# SCH_Gateway.net
KiCad netlist of a schematic drawn in EasyEDA
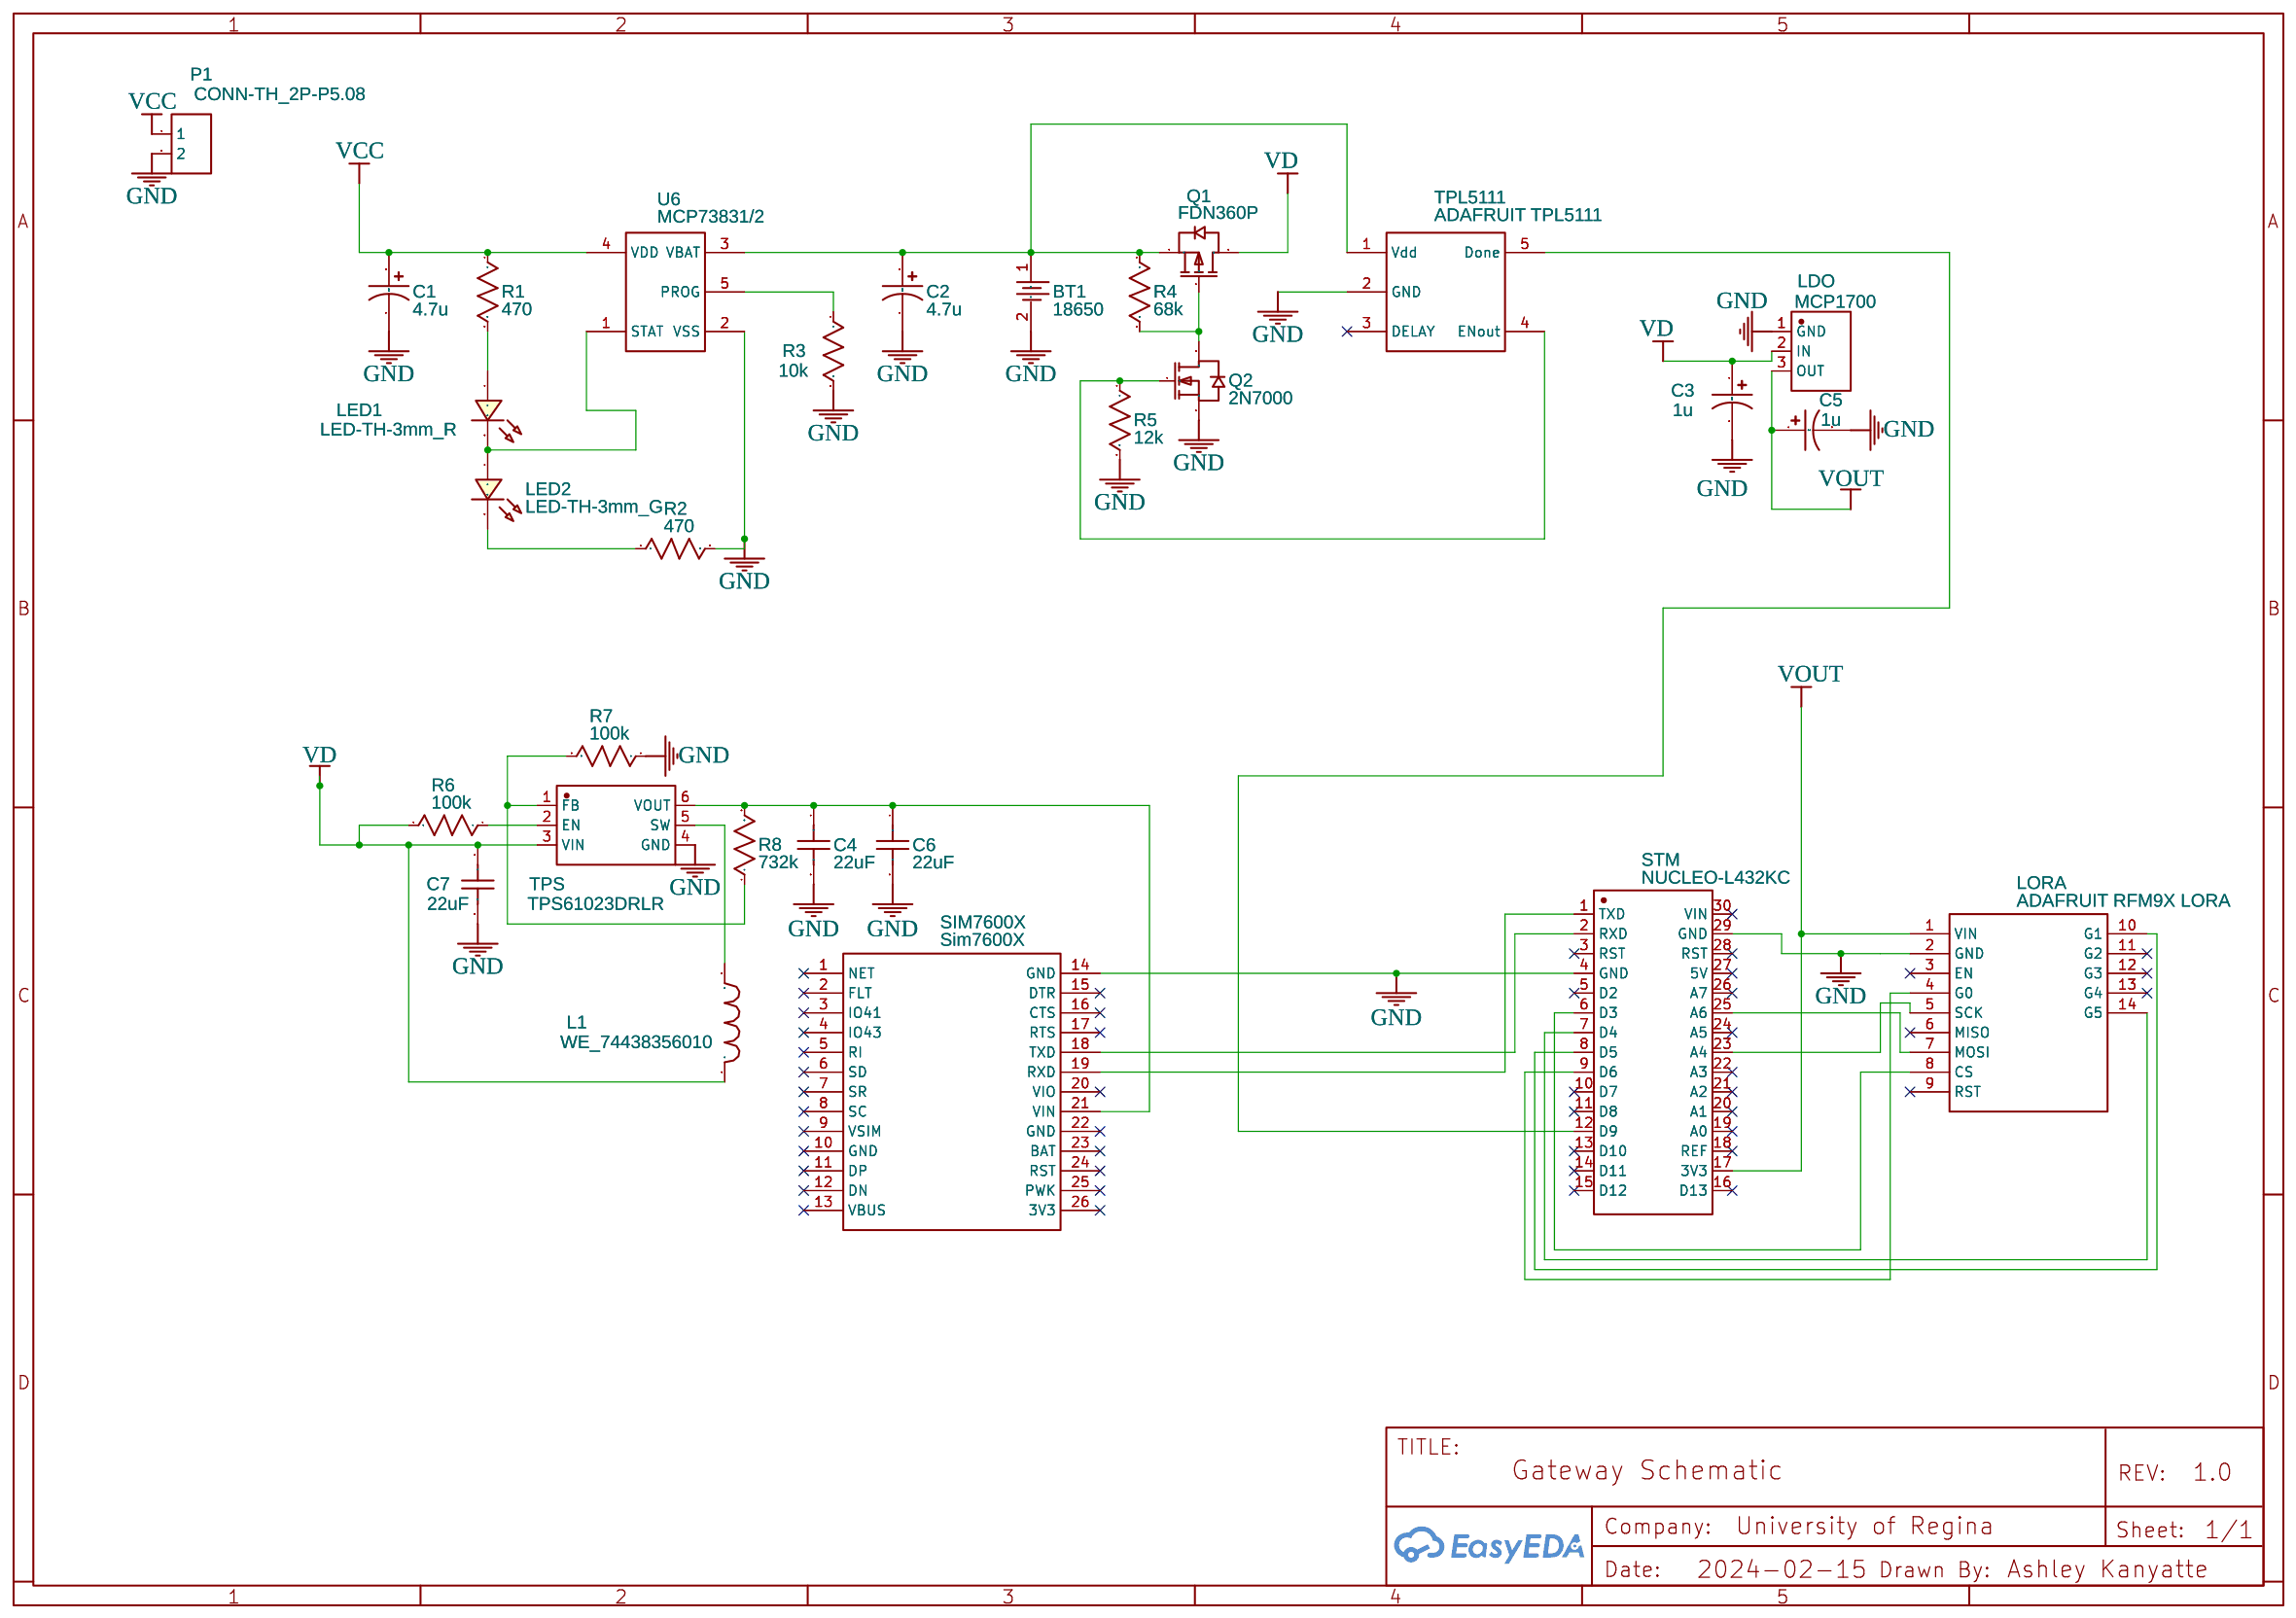
[diagram p0: schematic sheet]

(export (version "E")
  (design (tool "Eeschema 10.0.6"))
  (components
    (comp (ref "BT1")
      (value "18650")
      (fields
        (field (name "Manufacturer Part") "BH-18650-A5BJ001")
        (field (name "Manufacturer") "MYOUNG(美阳)")
      )
      (libsource (lib "") (part "BH-18650-A5BJ001"))
    )
    (comp (ref "C1") (value "4.7u") (libsource (lib "") (part "CE_TH_D5.0×F2.0_US_1")))
    (comp (ref "C2") (value "4.7u") (libsource (lib "") (part "CE_TH_D5.0×F2.0_US")))
    (comp (ref "C3") (value "1u") (libsource (lib "") (part "CE_TH_D5.0×F2.0_US")))
    (comp (ref "C4")
      (value "22uF")
      (fields
        (field (name "Manufacturer Part") "RDEC71E226K3K1H03B")
        (field (name "Manufacturer") "muRata(村田)")
      )
      (libsource (lib "") (part "RDEC71E226K3K1H03B"))
    )
    (comp (ref "C5") (value "1u") (libsource (lib "") (part "CE_TH_D5.0×F2.0_US_2")))
    (comp (ref "C6")
      (value "22uF")
      (fields
        (field (name "Manufacturer Part") "RDEC71E226K3K1H03B")
        (field (name "Manufacturer") "muRata(村田)")
      )
      (libsource (lib "") (part "RDEC71E226K3K1H03B"))
    )
    (comp (ref "C7")
      (value "22uF")
      (fields
        (field (name "Manufacturer Part") "RDEC71E226K3K1H03B")
        (field (name "Manufacturer") "muRata(村田)")
      )
      (libsource (lib "") (part "RDEC71E226K3K1H03B"))
    )
    (comp (ref "L1")
      (value "WE_74438356010")
      (fields
        (field (name "Manufacturer Part") "74438356010")
        (field (name "Manufacturer") "Wurth Elektronik")
      )
      (libsource (lib "") (part "WE_74438356010"))
    )
    (comp (ref "LDO")
      (value "MCP1700")
      (fields
        (field (name "Manufacturer Part") "MCP1700-3302E/TO")
        (field (name "Manufacturer") "MICROCHIP(美国微芯)")
      )
      (libsource (lib "") (part "MCP1700-3302E/TO"))
    )
    (comp (ref "LED1")
      (value "LED-TH-3mm_R")
      (fields
        (field (name "Manufacturer Part") "204-10SDRD/S530-A3-L")
        (field (name "Manufacturer") "EVERLIGHT(台湾亿光)")
      )
      (libsource (lib "") (part "LED-TH-3mm_R"))
    )
    (comp (ref "LED2")
      (value "LED-TH-3mm_G")
      (fields
        (field (name "Manufacturer Part") "204-10SYGD/S530-E3")
        (field (name "Manufacturer") "EVERLIGHT(台湾亿光)")
      )
      (libsource (lib "") (part "LED-TH-3mm_G"))
    )
    (comp (ref "LORA")
      (value "ADAFRUIT RFM9X LORA")
      (fields (field (name "Manufacturer Part") "3072") (field (name "Manufacturer") "Adafruit"))
      (libsource (lib "") (part "ADAFRUIT RFM9X LORA"))
    )
    (comp (ref "P1") (value "CONN-TH_2P-P5.08") (libsource (lib "") (part "CONN-TH_2P-P5.08")))
    (comp (ref "Q1")
      (value "FDN360P")
      (fields (field (name "Manufacturer") "onsemi(安森美)"))
      (libsource (lib "") (part "FDN360P"))
    )
    (comp (ref "Q2")
      (value "2N7000")
      (fields (field (name "Manufacturer") "CJ(江苏长电/长晶)"))
      (libsource (lib "") (part "2N7000"))
    )
    (comp (ref "R1") (value "470") (libsource (lib "") (part "R_AXIAL-0.4_US")))
    (comp (ref "R2") (value "470") (libsource (lib "") (part "R_AXIAL-0.4_US_1")))
    (comp (ref "R3") (value "10k") (libsource (lib "") (part "R_AXIAL-0.4_US")))
    (comp (ref "R4") (value "68k") (libsource (lib "") (part "R_AXIAL-0.4_US")))
    (comp (ref "R5") (value "12k") (libsource (lib "") (part "R_AXIAL-0.4_US")))
    (comp (ref "R6") (value "100k") (libsource (lib "") (part "R_AXIAL-0.4_US_3")))
    (comp (ref "R7") (value "100k") (libsource (lib "") (part "R_AXIAL-0.4_US_3")))
    (comp (ref "R8") (value "732k") (libsource (lib "") (part "R_AXIAL-0.4_US_2")))
    (comp (ref "SIM7600X") (value "Sim7600X") (libsource (lib "") (part "Sim7600X")))
    (comp (ref "STM")
      (value "NUCLEO-L432KC")
      (fields (field (name "Manufacturer") "ST(意法半导体)"))
      (libsource (lib "") (part "NUCLEO-L432KC"))
    )
    (comp (ref "TPL5111")
      (value "ADAFRUIT TPL5111")
      (fields (field (name "Manufacturer Part") "3435"))
      (libsource (lib "") (part "ADAFRUIT TPL5111"))
    )
    (comp (ref "TPS")
      (value "TPS61023DRLR")
      (fields (field (name "Manufacturer") "TI(德州仪器)"))
      (libsource (lib "") (part "TPS61023DRLR"))
    )
    (comp (ref "U6")
      (value "MCP73831/2")
      (fields (field (name "Manufacturer") "Microchip"))
      (libsource (lib "") (part "MCP73831/2"))
    )
  )
  (nets
    (net (code "1") (name "GND") (class "Default")
      (node (ref "BT1") (pin "2") (pinfunction "2_2") (pintype "input"))
      (node (ref "C1") (pin "2") (pinfunction "2_2") (pintype "unspecified"))
      (node (ref "C2") (pin "2") (pinfunction "2_2") (pintype "unspecified"))
      (node (ref "C3") (pin "2") (pinfunction "2_2") (pintype "unspecified"))
      (node (ref "C4") (pin "2") (pinfunction "2_2") (pintype "unspecified"))
      (node (ref "C5") (pin "2") (pinfunction "2_2") (pintype "unspecified"))
      (node (ref "C6") (pin "2") (pinfunction "2_2") (pintype "unspecified"))
      (node (ref "C7") (pin "2") (pinfunction "2_2") (pintype "unspecified"))
      (node (ref "LDO") (pin "1") (pinfunction "GND_1") (pintype "unspecified"))
      (node (ref "LORA") (pin "2") (pinfunction "GND_2") (pintype "unspecified"))
      (node (ref "P1") (pin "2") (pinfunction "2_2") (pintype "unspecified"))
      (node (ref "Q2") (pin "1") (pinfunction "S_1") (pintype "unspecified"))
      (node (ref "R2") (pin "2") (pinfunction "2_2") (pintype "unspecified"))
      (node (ref "R3") (pin "2") (pinfunction "2_2") (pintype "unspecified"))
      (node (ref "R5") (pin "2") (pinfunction "2_2") (pintype "unspecified"))
      (node (ref "R7") (pin "1") (pinfunction "1_1") (pintype "unspecified"))
      (node (ref "SIM7600X") (pin "14") (pinfunction "GND_14") (pintype "unspecified"))
      (node (ref "STM") (pin "29") (pinfunction "GND_29") (pintype "unspecified"))
      (node (ref "STM") (pin "4") (pinfunction "GND_4") (pintype "unspecified"))
      (node (ref "TPL5111") (pin "2") (pinfunction "GND_2") (pintype "unspecified"))
      (node (ref "TPS") (pin "4") (pinfunction "GND_4") (pintype "unspecified"))
      (node (ref "U6") (pin "2") (pinfunction "VSS_2") (pintype "unspecified"))
    )
    (net (code "2") (name "Net-(LED1-Pad1)") (class "Default")
      (node (ref "LED1") (pin "1") (pinfunction "1_1") (pintype "unspecified"))
      (node (ref "R1") (pin "2") (pinfunction "2_2") (pintype "unspecified"))
    )
    (net (code "3") (name "Net-(LED2-Pad2)") (class "Default")
      (node (ref "LED2") (pin "2") (pinfunction "2_2") (pintype "unspecified"))
      (node (ref "R2") (pin "1") (pinfunction "1_1") (pintype "unspecified"))
    )
    (net (code "4") (name "Net-(LORA-CS)") (class "Default")
      (node (ref "LORA") (pin "8") (pinfunction "CS_8") (pintype "unspecified"))
      (node (ref "STM") (pin "6") (pinfunction "D3_6") (pintype "unspecified"))
    )
    (net (code "5") (name "Net-(LORA-G0)") (class "Default")
      (node (ref "LORA") (pin "4") (pinfunction "G0_4") (pintype "unspecified"))
      (node (ref "STM") (pin "9") (pinfunction "D6_9") (pintype "unspecified"))
    )
    (net (code "6") (name "Net-(LORA-G1)") (class "Default")
      (node (ref "LORA") (pin "10") (pinfunction "G1_10") (pintype "unspecified"))
      (node (ref "STM") (pin "8") (pinfunction "D5_8") (pintype "unspecified"))
    )
    (net (code "7") (name "Net-(LORA-G5)") (class "Default")
      (node (ref "LORA") (pin "14") (pinfunction "G5_14") (pintype "unspecified"))
      (node (ref "STM") (pin "7") (pinfunction "D4_7") (pintype "unspecified"))
    )
    (net (code "8") (name "Net-(LORA-MOSI)") (class "Default")
      (node (ref "LORA") (pin "7") (pinfunction "MOSI_7") (pintype "unspecified"))
      (node (ref "STM") (pin "25") (pinfunction "A6_25") (pintype "unspecified"))
    )
    (net (code "9") (name "Net-(LORA-SCK)") (class "Default")
      (node (ref "LORA") (pin "5") (pinfunction "SCK_5") (pintype "unspecified"))
      (node (ref "STM") (pin "23") (pinfunction "A4_23") (pintype "unspecified"))
    )
    (net (code "10") (name "Net-(Q1-G)") (class "Default")
      (node (ref "Q1") (pin "1") (pinfunction "G_1") (pintype "unspecified"))
      (node (ref "Q2") (pin "3") (pinfunction "D_3") (pintype "unspecified"))
      (node (ref "R4") (pin "2") (pinfunction "2_2") (pintype "unspecified"))
    )
    (net (code "11") (name "Net-(Q1-S)") (class "Default")
      (node (ref "BT1") (pin "1") (pinfunction "1_1") (pintype "input"))
      (node (ref "C2") (pin "1") (pinfunction "1_1") (pintype "unspecified"))
      (node (ref "Q1") (pin "2") (pinfunction "S_2") (pintype "unspecified"))
      (node (ref "R4") (pin "1") (pinfunction "1_1") (pintype "unspecified"))
      (node (ref "TPL5111") (pin "1") (pinfunction "Vdd_1") (pintype "unspecified"))
      (node (ref "U6") (pin "3") (pinfunction "VBAT_3") (pintype "unspecified"))
    )
    (net (code "12") (name "Net-(Q2-G)") (class "Default")
      (node (ref "Q2") (pin "2") (pinfunction "G_2") (pintype "unspecified"))
      (node (ref "R5") (pin "1") (pinfunction "1_1") (pintype "unspecified"))
      (node (ref "TPL5111") (pin "4") (pinfunction "ENout_4") (pintype "unspecified"))
    )
    (net (code "13") (name "Net-(SIM7600X-RXD)") (class "Default")
      (node (ref "SIM7600X") (pin "19") (pinfunction "RXD_19") (pintype "unspecified"))
      (node (ref "STM") (pin "1") (pinfunction "TXD_1") (pintype "unspecified"))
    )
    (net (code "14") (name "Net-(SIM7600X-TXD)") (class "Default")
      (node (ref "SIM7600X") (pin "18") (pinfunction "TXD_18") (pintype "unspecified"))
      (node (ref "STM") (pin "2") (pinfunction "RXD_2") (pintype "unspecified"))
    )
    (net (code "15") (name "Net-(SIM7600X-VIN)") (class "Default")
      (node (ref "C4") (pin "1") (pinfunction "1_1") (pintype "unspecified"))
      (node (ref "C6") (pin "1") (pinfunction "1_1") (pintype "unspecified"))
      (node (ref "R8") (pin "2") (pinfunction "2_2") (pintype "unspecified"))
      (node (ref "SIM7600X") (pin "21") (pinfunction "VIN_21") (pintype "unspecified"))
      (node (ref "TPS") (pin "6") (pinfunction "VOUT_6") (pintype "unspecified"))
    )
    (net (code "16") (name "Net-(STM-D9)") (class "Default")
      (node (ref "STM") (pin "12") (pinfunction "D9_12") (pintype "unspecified"))
      (node (ref "TPL5111") (pin "5") (pinfunction "Done_5") (pintype "unspecified"))
    )
    (net (code "17") (name "Net-(TPS-EN)") (class "Default")
      (node (ref "R6") (pin "1") (pinfunction "1_1") (pintype "unspecified"))
      (node (ref "TPS") (pin "2") (pinfunction "EN_2") (pintype "unspecified"))
    )
    (net (code "18") (name "Net-(TPS-FB)") (class "Default")
      (node (ref "R7") (pin "2") (pinfunction "2_2") (pintype "unspecified"))
      (node (ref "R8") (pin "1") (pinfunction "1_1") (pintype "unspecified"))
      (node (ref "TPS") (pin "1") (pinfunction "FB_1") (pintype "unspecified"))
    )
    (net (code "19") (name "Net-(TPS-SW)") (class "Default")
      (node (ref "L1") (pin "1") (pinfunction "1_1") (pintype "unspecified"))
      (node (ref "TPS") (pin "5") (pinfunction "SW_5") (pintype "unspecified"))
    )
    (net (code "20") (name "Net-(U6-PROG)") (class "Default")
      (node (ref "R3") (pin "1") (pinfunction "1_1") (pintype "unspecified"))
      (node (ref "U6") (pin "5") (pinfunction "PROG_5") (pintype "unspecified"))
    )
    (net (code "21") (name "Net-(U6-STAT)") (class "Default")
      (node (ref "LED1") (pin "2") (pinfunction "2_2") (pintype "unspecified"))
      (node (ref "LED2") (pin "1") (pinfunction "1_1") (pintype "unspecified"))
      (node (ref "U6") (pin "1") (pinfunction "STAT_1") (pintype "unspecified"))
    )
    (net (code "22") (name "VCC") (class "Default")
      (node (ref "C1") (pin "1") (pinfunction "1_1") (pintype "unspecified"))
      (node (ref "P1") (pin "1") (pinfunction "1_1") (pintype "unspecified"))
      (node (ref "R1") (pin "1") (pinfunction "1_1") (pintype "unspecified"))
      (node (ref "U6") (pin "4") (pinfunction "VDD_4") (pintype "unspecified"))
    )
    (net (code "23") (name "VD") (class "Default")
      (node (ref "C3") (pin "1") (pinfunction "1_1") (pintype "unspecified"))
      (node (ref "C7") (pin "1") (pinfunction "1_1") (pintype "unspecified"))
      (node (ref "L1") (pin "2") (pinfunction "2_2") (pintype "unspecified"))
      (node (ref "LDO") (pin "2") (pinfunction "IN_2") (pintype "unspecified"))
      (node (ref "Q1") (pin "3") (pinfunction "D_3") (pintype "unspecified"))
      (node (ref "R6") (pin "2") (pinfunction "2_2") (pintype "unspecified"))
      (node (ref "TPS") (pin "3") (pinfunction "VIN_3") (pintype "unspecified"))
    )
    (net (code "24") (name "VOUT") (class "Default")
      (node (ref "C5") (pin "1") (pinfunction "1_1") (pintype "unspecified"))
      (node (ref "LDO") (pin "3") (pinfunction "OUT_3") (pintype "unspecified"))
      (node (ref "LORA") (pin "1") (pinfunction "VIN_1") (pintype "unspecified"))
      (node (ref "STM") (pin "17") (pinfunction "3V3_17") (pintype "unspecified"))
    )
    (net (code "25") (name "unconnected-(LORA-EN-Pad3)") (class "Default")
      (node (ref "LORA") (pin "3") (pinfunction "EN_3") (pintype "unspecified+no_connect"))
    )
    (net (code "26") (name "unconnected-(LORA-G2-Pad11)") (class "Default")
      (node (ref "LORA") (pin "11") (pinfunction "G2_11") (pintype "unspecified+no_connect"))
    )
    (net (code "27") (name "unconnected-(LORA-G3-Pad12)") (class "Default")
      (node (ref "LORA") (pin "12") (pinfunction "G3_12") (pintype "unspecified+no_connect"))
    )
    (net (code "28") (name "unconnected-(LORA-G4-Pad13)") (class "Default")
      (node (ref "LORA") (pin "13") (pinfunction "G4_13") (pintype "unspecified+no_connect"))
    )
    (net (code "29") (name "unconnected-(LORA-MISO-Pad6)") (class "Default")
      (node (ref "LORA") (pin "6") (pinfunction "MISO_6") (pintype "unspecified+no_connect"))
    )
    (net (code "30") (name "unconnected-(LORA-RST-Pad9)") (class "Default")
      (node (ref "LORA") (pin "9") (pinfunction "RST_9") (pintype "unspecified+no_connect"))
    )
    (net (code "31") (name "unconnected-(SIM7600X-3V3-Pad26)") (class "Default")
      (node (ref "SIM7600X") (pin "26") (pinfunction "3V3_26") (pintype "unspecified+no_connect"))
    )
    (net (code "32") (name "unconnected-(SIM7600X-BAT-Pad23)") (class "Default")
      (node (ref "SIM7600X") (pin "23") (pinfunction "BAT_23") (pintype "unspecified+no_connect"))
    )
    (net (code "33") (name "unconnected-(SIM7600X-CTS-Pad16)") (class "Default")
      (node (ref "SIM7600X") (pin "16") (pinfunction "CTS_16") (pintype "unspecified+no_connect"))
    )
    (net (code "34") (name "unconnected-(SIM7600X-DN-Pad12)") (class "Default")
      (node (ref "SIM7600X") (pin "12") (pinfunction "DN_12") (pintype "unspecified+no_connect"))
    )
    (net (code "35") (name "unconnected-(SIM7600X-DP-Pad11)") (class "Default")
      (node (ref "SIM7600X") (pin "11") (pinfunction "DP_11") (pintype "unspecified+no_connect"))
    )
    (net (code "36") (name "unconnected-(SIM7600X-DTR-Pad15)") (class "Default")
      (node (ref "SIM7600X") (pin "15") (pinfunction "DTR_15") (pintype "unspecified+no_connect"))
    )
    (net (code "37") (name "unconnected-(SIM7600X-FLT-Pad2)") (class "Default")
      (node (ref "SIM7600X") (pin "2") (pinfunction "FLT_2") (pintype "unspecified+no_connect"))
    )
    (net (code "38") (name "unconnected-(SIM7600X-GND-Pad10)") (class "Default")
      (node (ref "SIM7600X") (pin "10") (pinfunction "GND_10") (pintype "unspecified+no_connect"))
    )
    (net (code "39") (name "unconnected-(SIM7600X-GND-Pad22)") (class "Default")
      (node (ref "SIM7600X") (pin "22") (pinfunction "GND_22") (pintype "unspecified+no_connect"))
    )
    (net (code "40") (name "unconnected-(SIM7600X-IO41-Pad3)") (class "Default")
      (node (ref "SIM7600X") (pin "3") (pinfunction "IO41_3") (pintype "unspecified+no_connect"))
    )
    (net (code "41") (name "unconnected-(SIM7600X-IO43-Pad4)") (class "Default")
      (node (ref "SIM7600X") (pin "4") (pinfunction "IO43_4") (pintype "unspecified+no_connect"))
    )
    (net (code "42") (name "unconnected-(SIM7600X-NET-Pad1)") (class "Default")
      (node (ref "SIM7600X") (pin "1") (pinfunction "NET_1") (pintype "unspecified+no_connect"))
    )
    (net (code "43") (name "unconnected-(SIM7600X-PWK-Pad25)") (class "Default")
      (node (ref "SIM7600X") (pin "25") (pinfunction "PWK_25") (pintype "unspecified+no_connect"))
    )
    (net (code "44") (name "unconnected-(SIM7600X-RI-Pad5)") (class "Default")
      (node (ref "SIM7600X") (pin "5") (pinfunction "RI_5") (pintype "unspecified+no_connect"))
    )
    (net (code "45") (name "unconnected-(SIM7600X-RST-Pad24)") (class "Default")
      (node (ref "SIM7600X") (pin "24") (pinfunction "RST_24") (pintype "unspecified+no_connect"))
    )
    (net (code "46") (name "unconnected-(SIM7600X-RTS-Pad17)") (class "Default")
      (node (ref "SIM7600X") (pin "17") (pinfunction "RTS_17") (pintype "unspecified+no_connect"))
    )
    (net (code "47") (name "unconnected-(SIM7600X-SC-Pad8)") (class "Default")
      (node (ref "SIM7600X") (pin "8") (pinfunction "SC_8") (pintype "unspecified+no_connect"))
    )
    (net (code "48") (name "unconnected-(SIM7600X-SD-Pad6)") (class "Default")
      (node (ref "SIM7600X") (pin "6") (pinfunction "SD_6") (pintype "unspecified+no_connect"))
    )
    (net (code "49") (name "unconnected-(SIM7600X-SR-Pad7)") (class "Default")
      (node (ref "SIM7600X") (pin "7") (pinfunction "SR_7") (pintype "unspecified+no_connect"))
    )
    (net (code "50") (name "unconnected-(SIM7600X-VBUS-Pad13)") (class "Default")
      (node (ref "SIM7600X") (pin "13") (pinfunction "VBUS_13") (pintype "unspecified+no_connect"))
    )
    (net (code "51") (name "unconnected-(SIM7600X-VIO-Pad20)") (class "Default")
      (node (ref "SIM7600X") (pin "20") (pinfunction "VIO_20") (pintype "unspecified+no_connect"))
    )
    (net (code "52") (name "unconnected-(SIM7600X-VSIM-Pad9)") (class "Default")
      (node (ref "SIM7600X") (pin "9") (pinfunction "VSIM_9") (pintype "unspecified+no_connect"))
    )
    (net (code "53") (name "unconnected-(STM-5V-Pad27)") (class "Default")
      (node (ref "STM") (pin "27") (pinfunction "5V_27") (pintype "unspecified+no_connect"))
    )
    (net (code "54") (name "unconnected-(STM-A0-Pad19)") (class "Default")
      (node (ref "STM") (pin "19") (pinfunction "A0_19") (pintype "unspecified+no_connect"))
    )
    (net (code "55") (name "unconnected-(STM-A1-Pad20)") (class "Default")
      (node (ref "STM") (pin "20") (pinfunction "A1_20") (pintype "unspecified+no_connect"))
    )
    (net (code "56") (name "unconnected-(STM-A2-Pad21)") (class "Default")
      (node (ref "STM") (pin "21") (pinfunction "A2_21") (pintype "unspecified+no_connect"))
    )
    (net (code "57") (name "unconnected-(STM-A3-Pad22)") (class "Default")
      (node (ref "STM") (pin "22") (pinfunction "A3_22") (pintype "unspecified+no_connect"))
    )
    (net (code "58") (name "unconnected-(STM-A5-Pad24)") (class "Default")
      (node (ref "STM") (pin "24") (pinfunction "A5_24") (pintype "unspecified+no_connect"))
    )
    (net (code "59") (name "unconnected-(STM-A7-Pad26)") (class "Default")
      (node (ref "STM") (pin "26") (pinfunction "A7_26") (pintype "unspecified+no_connect"))
    )
    (net (code "60") (name "unconnected-(STM-D2-Pad5)") (class "Default")
      (node (ref "STM") (pin "5") (pinfunction "D2_5") (pintype "unspecified+no_connect"))
    )
    (net (code "61") (name "unconnected-(STM-D7-Pad10)") (class "Default")
      (node (ref "STM") (pin "10") (pinfunction "D7_10") (pintype "unspecified+no_connect"))
    )
    (net (code "62") (name "unconnected-(STM-D8-Pad11)") (class "Default")
      (node (ref "STM") (pin "11") (pinfunction "D8_11") (pintype "unspecified+no_connect"))
    )
    (net (code "63") (name "unconnected-(STM-D10-Pad13)") (class "Default")
      (node (ref "STM") (pin "13") (pinfunction "D10_13") (pintype "unspecified+no_connect"))
    )
    (net (code "64") (name "unconnected-(STM-D11-Pad14)") (class "Default")
      (node (ref "STM") (pin "14") (pinfunction "D11_14") (pintype "unspecified+no_connect"))
    )
    (net (code "65") (name "unconnected-(STM-D12-Pad15)") (class "Default")
      (node (ref "STM") (pin "15") (pinfunction "D12_15") (pintype "unspecified+no_connect"))
    )
    (net (code "66") (name "unconnected-(STM-D13-Pad16)") (class "Default")
      (node (ref "STM") (pin "16") (pinfunction "D13_16") (pintype "unspecified+no_connect"))
    )
    (net (code "67") (name "unconnected-(STM-REF-Pad18)") (class "Default")
      (node (ref "STM") (pin "18") (pinfunction "REF_18") (pintype "unspecified+no_connect"))
    )
    (net (code "68") (name "unconnected-(STM-RST-Pad3)") (class "Default")
      (node (ref "STM") (pin "3") (pinfunction "RST_3") (pintype "unspecified+no_connect"))
    )
    (net (code "69") (name "unconnected-(STM-RST-Pad28)") (class "Default")
      (node (ref "STM") (pin "28") (pinfunction "RST_28") (pintype "unspecified+no_connect"))
    )
    (net (code "70") (name "unconnected-(STM-VIN-Pad30)") (class "Default")
      (node (ref "STM") (pin "30") (pinfunction "VIN_30") (pintype "unspecified+no_connect"))
    )
    (net (code "71") (name "unconnected-(TPL5111-DELAY-Pad3)") (class "Default")
      (node (ref "TPL5111") (pin "3") (pinfunction "DELAY_3") (pintype "unspecified+no_connect"))
    )
  )
)
